# STM32F4_OSD_V12.net
KiCad netlist of a schematic drawn in Altium Designer
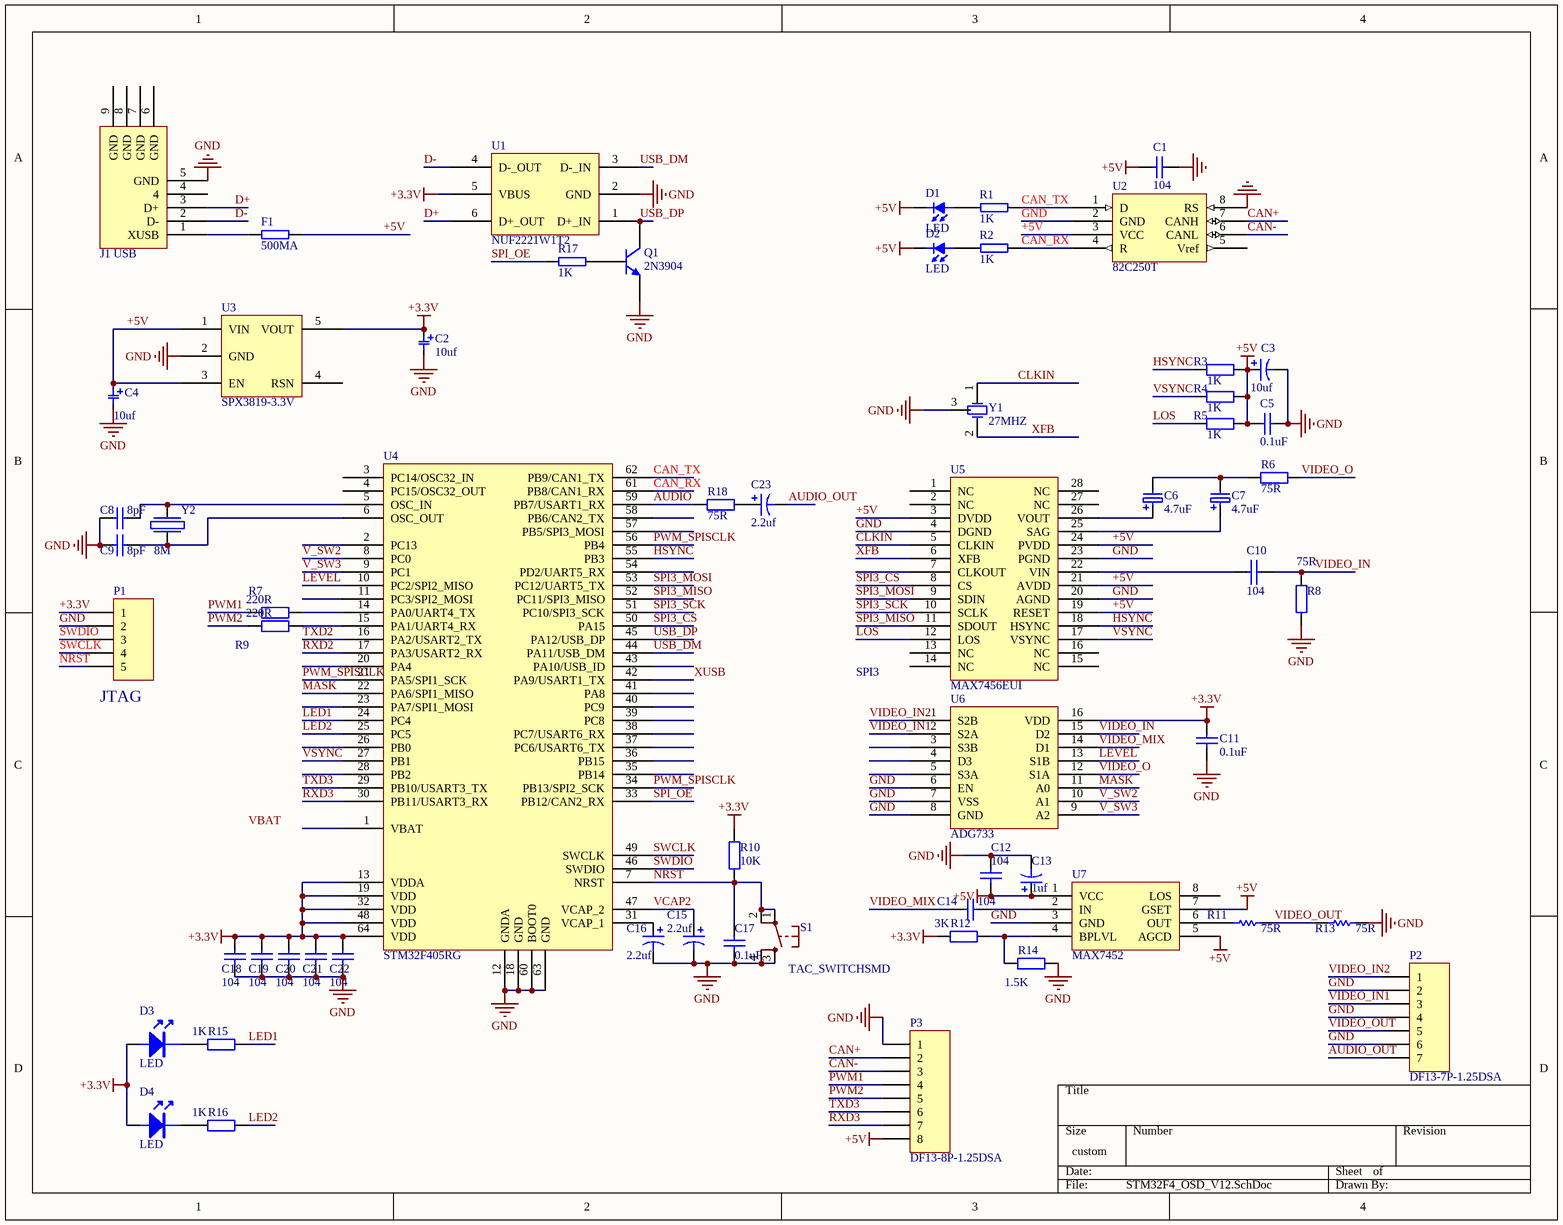
[diagram p0: STM32F4_OSD_V12.SchDoc]

(export (version "E")
  (design (tool "Eeschema 10.0.6"))
  (components
    (comp (ref "C1")
      (value "104")
      (footprint "0603C")
      (description "Capacitor")
      (fields (field (name "PUBLISHER") "Altium Limited"))
      (libsource (lib "") (part "CAP_1"))
    )
    (comp (ref "C2") (value "10uf") (footprint "0805") (libsource (lib "电阻电容") (part "ECAP")))
    (comp (ref "C3")
      (value "10uf")
      (footprint "0603C")
      (description "Polarized Capacitor (Radial)")
      (libsource (lib "Miscellaneous Devices") (part "Cap Pol1"))
    )
    (comp (ref "C4") (value "10uf") (footprint "0805") (libsource (lib "电阻电容") (part "ECAP")))
    (comp (ref "C5")
      (value "0.1uF")
      (footprint "0402-CAP")
      (description "Capacitor")
      (fields (field (name "Comment") "Cap") (field (name "PUBLISHER") "Altium Limited"))
      (libsource (lib "Miscellaneous Devices") (part "Cap"))
    )
    (comp (ref "C6")
      (value "4.7uF")
      (footprint "0603C")
      (description "Electrolytic Capacitor 1")
      (libsource (lib "QT_SCH_V2") (part "ELECTRO1"))
    )
    (comp (ref "C7")
      (value "4.7uF")
      (footprint "0603C")
      (description "Electrolytic Capacitor 1")
      (libsource (lib "QT_SCH_V2") (part "ELECTRO1"))
    )
    (comp (ref "C8")
      (value "8pF")
      (footprint "0402-CAP")
      (description "Capacitor")
      (libsource (lib "EMotus Components") (part "CAP0805"))
    )
    (comp (ref "C9")
      (value "8pF")
      (footprint "0402-CAP")
      (description "Capacitor")
      (libsource (lib "EMotus Components") (part "CAP0805"))
    )
    (comp (ref "C10")
      (value "104")
      (footprint "0402-CAP")
      (description "Capacitor")
      (libsource (lib "*") (part "CAP"))
    )
    (comp (ref "C11")
      (value "0.1uF")
      (footprint "0402-CAP")
      (description "Capacitor")
      (fields (field (name "Comment") "Cap") (field (name "PUBLISHER") "Altium Limited"))
      (libsource (lib "Miscellaneous Devices") (part "Cap"))
    )
    (comp (ref "C12")
      (value "104")
      (footprint "0402-CAP")
      (description "Capacitor")
      (libsource (lib "Miscellaneous Devices") (part "Cap"))
    )
    (comp (ref "C13")
      (value "1uf")
      (footprint "0603C")
      (description "Polarized Capacitor (Radial)")
      (libsource (lib "Miscellaneous Devices") (part "Cap Pol1"))
    )
    (comp (ref "C14")
      (value "104")
      (footprint "0402-CAP")
      (description "Capacitor")
      (libsource (lib "Miscellaneous Devices") (part "Cap"))
    )
    (comp (ref "C15")
      (value "2.2uf")
      (footprint "0603C")
      (description "Polarized Capacitor (Radial)")
      (libsource (lib "Miscellaneous Devices") (part "Cap Pol1"))
    )
    (comp (ref "C16")
      (value "2.2uf")
      (footprint "0603C")
      (description "Polarized Capacitor (Radial)")
      (libsource (lib "Miscellaneous Devices") (part "Cap Pol1"))
    )
    (comp (ref "C17")
      (value "0.1uF")
      (footprint "0402-CAP")
      (description "Capacitor")
      (fields (field (name "Comment") "Cap") (field (name "PUBLISHER") "Altium Limited"))
      (libsource (lib "Miscellaneous Devices") (part "Cap"))
    )
    (comp (ref "C18")
      (value "104")
      (footprint "0402-CAP")
      (description "Capacitor")
      (libsource (lib "Miscellaneous Devices") (part "Cap"))
    )
    (comp (ref "C19")
      (value "104")
      (footprint "0402-CAP")
      (description "Capacitor")
      (libsource (lib "Miscellaneous Devices") (part "Cap"))
    )
    (comp (ref "C20")
      (value "104")
      (footprint "0402-CAP")
      (description "Capacitor")
      (libsource (lib "Miscellaneous Devices") (part "Cap"))
    )
    (comp (ref "C21")
      (value "104")
      (footprint "0402-CAP")
      (description "Capacitor")
      (libsource (lib "Miscellaneous Devices") (part "Cap"))
    )
    (comp (ref "C22")
      (value "104")
      (footprint "0402-CAP")
      (description "Capacitor")
      (libsource (lib "Miscellaneous Devices") (part "Cap"))
    )
    (comp (ref "C23")
      (value "2.2uf")
      (footprint "0603C")
      (description "Polarized Capacitor (Radial)")
      (libsource (lib "Miscellaneous Devices") (part "Cap Pol1"))
    )
    (comp (ref "D1") (value "LED") (footprint "0603-LED") (libsource (lib "原理图库") (part "LED")))
    (comp (ref "D2") (value "LED") (footprint "0603-LED") (libsource (lib "原理图库") (part "LED")))
    (comp (ref "D3") (value "LED") (footprint "0603-LED") (libsource (lib "MySch") (part "LED")))
    (comp (ref "D4") (value "LED") (footprint "0603-LED") (libsource (lib "MySch") (part "LED")))
    (comp (ref "F1") (value "500MA") (footprint "PTC-1206") (libsource (lib "DXP常用原理图库.libsch") (part "RES")))
    (comp (ref "J1")
      (value "USB")
      (footprint "MOLEX_MICRO_USB_AB_BOTTOM_MOUNT")
      (libsource (lib "Schlib1") (part "USB"))
    )
    (comp (ref "P1")
      (value "JTAG")
      (footprint "DF13-5P-1.25DSA")
      (description "Header, 5-Pin")
      (libsource (lib "Miscellaneous Connectors") (part "Header 5"))
    )
    (comp (ref "P2")
      (value "DF13-7P-1.25DSA")
      (footprint "DF13C-7P-1.25V")
      (description "Header, 7-Pin")
      (libsource (lib "Miscellaneous Connectors") (part "Header 7"))
    )
    (comp (ref "P3")
      (value "DF13-8P-1.25DSA")
      (footprint "DF13C-8P-1.25V")
      (description "Header, 8-Pin")
      (libsource (lib "Miscellaneous Connectors") (part "Header 8"))
    )
    (comp (ref "Q1")
      (value "2N3904")
      (footprint "TO-92A")
      (description "NPN General Purpose Amplifier")
      (fields (field (name "PUBLISHER") "Altium Limited"))
      (libsource (lib "Miscellaneous Devices") (part "2N3904"))
    )
    (comp (ref "R1") (value "1K") (footprint "0402-RES") (libsource (lib "DXP常用原理图库.libsch") (part "RES")))
    (comp (ref "R2") (value "1K") (footprint "0402-RES") (libsource (lib "DXP常用原理图库.libsch") (part "RES")))
    (comp (ref "R3")
      (value "1K")
      (footprint "0402-RES")
      (description "Resistor")
      (libsource (lib "") (part "Res2_1"))
    )
    (comp (ref "R4")
      (value "1K")
      (footprint "0402-RES")
      (description "Resistor")
      (libsource (lib "") (part "Res2_1"))
    )
    (comp (ref "R5")
      (value "1K")
      (footprint "0402-RES")
      (description "Resistor")
      (libsource (lib "") (part "Res2_1"))
    )
    (comp (ref "R6")
      (value "75R")
      (footprint "0402-RES")
      (description "Resistor")
      (libsource (lib "") (part "Res2_1"))
    )
    (comp (ref "R7")
      (value "220R")
      (footprint "0402-RES")
      (description "Resistor")
      (libsource (lib "Miscellaneous Devices") (part "Res2"))
    )
    (comp (ref "R8")
      (value "75R")
      (footprint "0402-RES")
      (description "Resistor")
      (libsource (lib "") (part "Res2_2"))
    )
    (comp (ref "R9")
      (value "220R")
      (footprint "0402-RES")
      (description "Resistor")
      (libsource (lib "Miscellaneous Devices") (part "Res2"))
    )
    (comp (ref "R10")
      (value "10K")
      (footprint "0402-RES")
      (description "Resistor")
      (libsource (lib "") (part "Res2_2"))
    )
    (comp (ref "R11")
      (value "75R")
      (footprint "0402-RES")
      (description "Resistor")
      (libsource (lib "Miscellaneous Devices") (part "Res1"))
    )
    (comp (ref "R12")
      (value "3K")
      (footprint "0402-RES")
      (description "Resistor")
      (libsource (lib "Miscellaneous Devices") (part "Res2"))
    )
    (comp (ref "R13")
      (value "75R")
      (footprint "0402-RES")
      (description "Resistor")
      (libsource (lib "Miscellaneous Devices") (part "Res1"))
    )
    (comp (ref "R14")
      (value "1.5K")
      (footprint "0402-RES")
      (description "Resistor")
      (libsource (lib "Miscellaneous Devices") (part "Res2"))
    )
    (comp (ref "R15")
      (value "1K")
      (footprint "0402-RES")
      (description "Resistor")
      (libsource (lib "Miscellaneous Devices") (part "Res2"))
    )
    (comp (ref "R16")
      (value "1K")
      (footprint "0402-RES")
      (description "Resistor")
      (libsource (lib "Miscellaneous Devices") (part "Res2"))
    )
    (comp (ref "R17") (value "1K") (footprint "0402-RES") (libsource (lib "DXP常用原理图库.libsch") (part "RES")))
    (comp (ref "R18")
      (value "75R")
      (footprint "0402-RES")
      (description "Resistor")
      (libsource (lib "Miscellaneous Devices") (part "Res2"))
    )
    (comp (ref "S1")
      (value "TAC_SWITCHSMD")
      (footprint "EVQP7J01K")
      (libsource (lib "DIYdrones3") (part "TAC_SWITCHSMD"))
    )
    (comp (ref "U1")
      (value "NUF2221W1T2")
      (footprint "SOT363")
      (libsource (lib "Schlib1") (part "NUF2221W1T2"))
    )
    (comp (ref "U2") (value "82C250T") (footprint "SO-8N") (libsource (lib "*") (part "SN65HVD230D")))
    (comp (ref "U3") (value "SPX3819-3.3V") (footprint "SOT23-5") (libsource (lib "原理图库") (part "SP6201")))
    (comp (ref "U4")
      (value "STM32F405RG")
      (footprint "LQFP64")
      (libsource (lib "Schlib1") (part "STM32F405RG"))
    )
    (comp (ref "U5") (value "MAX7456EUI") (footprint "SSOP-28") (libsource (lib "Schlib1") (part "MAX7456")))
    (comp (ref "U6") (value "ADG733") (footprint "TSOP16") (libsource (lib "Schlib1") (part "ADG733")))
    (comp (ref "U7") (value "MAX7452") (footprint "SOIC-SN8_N") (libsource (lib "Schlib1") (part "MAX7452")))
    (comp (ref "Y1") (value "27MHZ") (footprint "27MHZ") (libsource (lib "晶振滤波器") (part "晶振3脚")))
    (comp (ref "Y2")
      (value "8M")
      (footprint "OSCILLATOR-3.2X2.5")
      (description "7B-8.000MAAJ-T")
      (libsource (lib "passive") (part "ZQ_KX12B"))
    )
  )
  (nets
    (net (code "1") (name "+3.3V") (class "Default")
      (node (ref "C11") (pin "2") (pinfunction "2_2") (pintype "passive"))
      (node (ref "C18") (pin "2") (pinfunction "2_2") (pintype "passive"))
      (node (ref "C19") (pin "2") (pinfunction "2_2") (pintype "passive"))
      (node (ref "C2") (pin "2") (pintype "passive"))
      (node (ref "C20") (pin "2") (pinfunction "2_2") (pintype "passive"))
      (node (ref "C21") (pin "2") (pinfunction "2_2") (pintype "passive"))
      (node (ref "C22") (pin "2") (pinfunction "2_2") (pintype "passive"))
      (node (ref "D3") (pin "1") (pinfunction "1_1") (pintype "passive"))
      (node (ref "D4") (pin "1") (pinfunction "1_1") (pintype "passive"))
      (node (ref "P1") (pin "1") (pinfunction "1_1") (pintype "passive"))
      (node (ref "R10") (pin "2") (pinfunction "2_2") (pintype "passive"))
      (node (ref "R12") (pin "2") (pinfunction "2_2") (pintype "passive"))
      (node (ref "U1") (pin "5") (pinfunction "VBUS_5") (pintype "passive"))
      (node (ref "U3") (pin "5") (pinfunction "VOUT_5") (pintype "passive"))
      (node (ref "U4") (pin "13") (pinfunction "VDDA_13") (pintype "passive"))
      (node (ref "U4") (pin "19") (pinfunction "VDD_19") (pintype "passive"))
      (node (ref "U4") (pin "32") (pinfunction "VDD_32") (pintype "passive"))
      (node (ref "U4") (pin "48") (pinfunction "VDD_48") (pintype "passive"))
      (node (ref "U4") (pin "64") (pinfunction "VDD_64") (pintype "passive"))
      (node (ref "U6") (pin "16") (pinfunction "VDD_16") (pintype "passive"))
    )
    (net (code "2") (name "+5V") (class "Default")
      (node (ref "C1") (pin "2") (pinfunction "2_2") (pintype "passive"))
      (node (ref "C12") (pin "1") (pinfunction "1_1") (pintype "passive"))
      (node (ref "C13") (pin "1") (pinfunction "1_1") (pintype "passive"))
      (node (ref "C3") (pin "1") (pinfunction "1_1") (pintype "passive"))
      (node (ref "C4") (pin "2") (pintype "passive"))
      (node (ref "C5") (pin "1") (pinfunction "1_1") (pintype "passive"))
      (node (ref "D1") (pin "2") (pinfunction "2_2") (pintype "passive"))
      (node (ref "D2") (pin "2") (pinfunction "2_2") (pintype "passive"))
      (node (ref "F1") (pin "1") (pinfunction "1_1") (pintype "passive"))
      (node (ref "P3") (pin "8") (pinfunction "8_8") (pintype "passive"))
      (node (ref "R3") (pin "2") (pinfunction "2_2") (pintype "passive"))
      (node (ref "R4") (pin "2") (pinfunction "2_2") (pintype "passive"))
      (node (ref "R5") (pin "2") (pinfunction "2_2") (pintype "passive"))
      (node (ref "U2") (pin "3") (pinfunction "VCC_3") (pintype "power_in"))
      (node (ref "U3") (pin "1") (pinfunction "VIN_1") (pintype "passive"))
      (node (ref "U3") (pin "3") (pinfunction "EN_3") (pintype "passive"))
      (node (ref "U5") (pin "19") (pinfunction "RESET_19") (pintype "passive"))
      (node (ref "U5") (pin "21") (pinfunction "AVDD_21") (pintype "passive"))
      (node (ref "U5") (pin "24") (pinfunction "PVDD_24") (pintype "passive"))
      (node (ref "U5") (pin "3") (pinfunction "DVDD_3") (pintype "passive"))
      (node (ref "U7") (pin "1") (pinfunction "VCC_1") (pintype "passive"))
      (node (ref "U7") (pin "5") (pinfunction "AGCD_5") (pintype "passive"))
      (node (ref "U7") (pin "7") (pinfunction "GSET_7") (pintype "passive"))
    )
    (net (code "3") (name "/AUDIO") (class "Default")
      (node (ref "R18") (pin "2") (pinfunction "2_2") (pintype "passive"))
      (node (ref "U4") (pin "59") (pinfunction "PB7/USART1_RX_59") (pintype "passive"))
    )
    (net (code "4") (name "/AUDIO_OUT") (class "Default")
      (node (ref "C23") (pin "2") (pinfunction "2_2") (pintype "passive"))
      (node (ref "P2") (pin "7") (pinfunction "7_7") (pintype "passive"))
    )
    (net (code "5") (name "/CAN+") (class "Default")
      (node (ref "P3") (pin "2") (pinfunction "2_2") (pintype "passive"))
      (node (ref "U2") (pin "7") (pinfunction "CANH_7") (pintype "bidirectional"))
    )
    (net (code "6") (name "/CAN-") (class "Default")
      (node (ref "P3") (pin "3") (pinfunction "3_3") (pintype "passive"))
      (node (ref "U2") (pin "6") (pinfunction "CANL_6") (pintype "bidirectional"))
    )
    (net (code "7") (name "/CAN_RX") (class "Default")
      (node (ref "R2") (pin "2") (pinfunction "2_2") (pintype "passive"))
      (node (ref "U2") (pin "4") (pinfunction "R_4") (pintype "output"))
      (node (ref "U4") (pin "61") (pinfunction "PB8/CAN1_RX_61") (pintype "passive"))
    )
    (net (code "8") (name "/CAN_TX") (class "Default")
      (node (ref "R1") (pin "2") (pinfunction "2_2") (pintype "passive"))
      (node (ref "U2") (pin "1") (pinfunction "D_1") (pintype "input"))
      (node (ref "U4") (pin "62") (pinfunction "PB9/CAN1_TX_62") (pintype "passive"))
    )
    (net (code "9") (name "/CLKIN") (class "Default")
      (node (ref "U5") (pin "5") (pinfunction "CLKIN_5") (pintype "passive"))
      (node (ref "Y1") (pin "1") (pinfunction "1_1") (pintype "passive"))
    )
    (net (code "10") (name "/D+") (class "Default")
      (node (ref "J1") (pin "3") (pinfunction "D+_3") (pintype "passive"))
      (node (ref "U1") (pin "6") (pinfunction "D+_OUT_6") (pintype "passive"))
    )
    (net (code "11") (name "/D-") (class "Default")
      (node (ref "J1") (pin "2") (pinfunction "D-_2") (pintype "passive"))
      (node (ref "U1") (pin "4") (pinfunction "D-_OUT_4") (pintype "passive"))
    )
    (net (code "12") (name "/HSYNC") (class "Default")
      (node (ref "R3") (pin "1") (pinfunction "1_1") (pintype "passive"))
      (node (ref "U4") (pin "55") (pinfunction "PB3_55") (pintype "passive"))
      (node (ref "U5") (pin "18") (pinfunction "HSYNC_18") (pintype "passive"))
    )
    (net (code "13") (name "/LED1") (class "Default")
      (node (ref "R15") (pin "1") (pinfunction "1_1") (pintype "passive"))
      (node (ref "U4") (pin "24") (pinfunction "PC4_24") (pintype "passive"))
    )
    (net (code "14") (name "/LED2") (class "Default")
      (node (ref "R16") (pin "1") (pinfunction "1_1") (pintype "passive"))
      (node (ref "U4") (pin "25") (pinfunction "PC5_25") (pintype "passive"))
    )
    (net (code "15") (name "/LEVEL") (class "Default")
      (node (ref "U4") (pin "10") (pinfunction "PC2/SPI2_MISO_10") (pintype "passive"))
      (node (ref "U6") (pin "13") (pinfunction "S1B_13") (pintype "passive"))
    )
    (net (code "16") (name "/LOS") (class "Default")
      (node (ref "R5") (pin "1") (pinfunction "1_1") (pintype "passive"))
      (node (ref "U5") (pin "12") (pinfunction "LOS_12") (pintype "passive"))
    )
    (net (code "17") (name "/MASK") (class "Default")
      (node (ref "U4") (pin "22") (pinfunction "PA6/SPI1_MISO_22") (pintype "passive"))
      (node (ref "U6") (pin "11") (pinfunction "A0_11") (pintype "passive"))
    )
    (net (code "18") (name "/NRST") (class "Default")
      (node (ref "C17") (pin "2") (pinfunction "2_2") (pintype "passive"))
      (node (ref "P1") (pin "5") (pinfunction "5_5") (pintype "passive"))
      (node (ref "R10") (pin "1") (pinfunction "1_1") (pintype "passive"))
      (node (ref "S1") (pin "1") (pinfunction "1_1") (pintype "passive"))
      (node (ref "S1") (pin "2") (pinfunction "2_2") (pintype "passive"))
      (node (ref "U4") (pin "7") (pinfunction "NRST_7") (pintype "passive"))
    )
    (net (code "19") (name "/PWM1") (class "Default")
      (node (ref "P3") (pin "4") (pinfunction "4_4") (pintype "passive"))
      (node (ref "R7") (pin "2") (pinfunction "2_2") (pintype "passive"))
    )
    (net (code "20") (name "/PWM2") (class "Default")
      (node (ref "P3") (pin "5") (pinfunction "5_5") (pintype "passive"))
      (node (ref "R9") (pin "2") (pinfunction "2_2") (pintype "passive"))
    )
    (net (code "21") (name "/PWM_SPISCLK") (class "Default")
      (node (ref "U4") (pin "21") (pinfunction "PA5/SPI1_SCK_21") (pintype "passive"))
      (node (ref "U4") (pin "34") (pinfunction "PB13/SPI2_SCK_34") (pintype "passive"))
      (node (ref "U4") (pin "56") (pinfunction "PB4_56") (pintype "passive"))
    )
    (net (code "22") (name "/RXD2") (class "Default")
      (node (ref "U4") (pin "17") (pinfunction "PA3/USART2_RX_17") (pintype "passive"))
    )
    (net (code "23") (name "/RXD3") (class "Default")
      (node (ref "P3") (pin "7") (pinfunction "7_7") (pintype "passive"))
      (node (ref "U4") (pin "30") (pinfunction "PB11/USART3_RX_30") (pintype "passive"))
    )
    (net (code "24") (name "/SPI3_CS") (class "Default")
      (node (ref "U4") (pin "50") (pinfunction "PA15_50") (pintype "passive"))
      (node (ref "U5") (pin "8") (pinfunction "CS_8") (pintype "passive"))
    )
    (net (code "25") (name "/SPI3_MISO") (class "Default")
      (node (ref "U4") (pin "52") (pinfunction "PC11/SPI3_MISO_52") (pintype "passive"))
      (node (ref "U5") (pin "11") (pinfunction "SDOUT_11") (pintype "passive"))
    )
    (net (code "26") (name "/SPI3_MOSI") (class "Default")
      (node (ref "U4") (pin "53") (pinfunction "PC12/UART5_TX_53") (pintype "passive"))
      (node (ref "U5") (pin "9") (pinfunction "SDIN_9") (pintype "passive"))
    )
    (net (code "27") (name "/SPI3_SCK") (class "Default")
      (node (ref "U4") (pin "51") (pinfunction "PC10/SPI3_SCK_51") (pintype "passive"))
      (node (ref "U5") (pin "10") (pinfunction "SCLK_10") (pintype "passive"))
    )
    (net (code "28") (name "/SPI_OE") (class "Default")
      (node (ref "R17") (pin "1") (pinfunction "1_1") (pintype "passive"))
      (node (ref "U4") (pin "33") (pinfunction "PB12/CAN2_RX_33") (pintype "passive"))
    )
    (net (code "29") (name "/SWCLK") (class "Default")
      (node (ref "P1") (pin "4") (pinfunction "4_4") (pintype "passive"))
      (node (ref "U4") (pin "49") (pinfunction "SWCLK_49") (pintype "passive"))
    )
    (net (code "30") (name "/SWDIO") (class "Default")
      (node (ref "P1") (pin "3") (pinfunction "3_3") (pintype "passive"))
      (node (ref "U4") (pin "46") (pinfunction "SWDIO_46") (pintype "passive"))
    )
    (net (code "31") (name "/TXD2") (class "Default")
      (node (ref "U4") (pin "16") (pinfunction "PA2/USART2_TX_16") (pintype "passive"))
    )
    (net (code "32") (name "/TXD3") (class "Default")
      (node (ref "P3") (pin "6") (pinfunction "6_6") (pintype "passive"))
      (node (ref "U4") (pin "29") (pinfunction "PB10/USART3_TX_29") (pintype "passive"))
    )
    (net (code "33") (name "/USB_DM") (class "Default")
      (node (ref "U1") (pin "3") (pinfunction "D-_IN_3") (pintype "passive"))
      (node (ref "U4") (pin "44") (pinfunction "PA11/USB_DM_44") (pintype "passive"))
    )
    (net (code "34") (name "/USB_DP") (class "Default")
      (node (ref "Q1") (pin "3") (pinfunction "C_3") (pintype "passive"))
      (node (ref "U1") (pin "1") (pinfunction "D+_IN_1") (pintype "passive"))
      (node (ref "U4") (pin "45") (pinfunction "PA12/USB_DP_45") (pintype "passive"))
    )
    (net (code "36") (name "/VCAP2") (class "Default")
      (node (ref "C15") (pin "1") (pinfunction "1_1") (pintype "passive"))
      (node (ref "U4") (pin "47") (pinfunction "VCAP_2_47") (pintype "passive"))
    )
    (net (code "37") (name "/VIDEO_IN") (class "Default")
      (node (ref "C10") (pin "2") (pinfunction "2_2") (pintype "passive"))
      (node (ref "R8") (pin "2") (pinfunction "2_2") (pintype "passive"))
      (node (ref "U6") (pin "15") (pinfunction "D2_15") (pintype "passive"))
    )
    (net (code "38") (name "/VIDEO_IN1") (class "Default")
      (node (ref "P2") (pin "3") (pinfunction "3_3") (pintype "passive"))
      (node (ref "U6") (pin "2") (pinfunction "S2A_2") (pintype "passive"))
    )
    (net (code "39") (name "/VIDEO_IN2") (class "Default")
      (node (ref "P2") (pin "1") (pinfunction "1_1") (pintype "passive"))
      (node (ref "U6") (pin "1") (pinfunction "S2B_1") (pintype "passive"))
    )
    (net (code "40") (name "/VIDEO_MIX") (class "Default")
      (node (ref "C14") (pin "1") (pinfunction "1_1") (pintype "passive"))
      (node (ref "U6") (pin "14") (pinfunction "D1_14") (pintype "passive"))
    )
    (net (code "41") (name "/VIDEO_O") (class "Default")
      (node (ref "R6") (pin "2") (pinfunction "2_2") (pintype "passive"))
      (node (ref "U6") (pin "12") (pinfunction "S1A_12") (pintype "passive"))
    )
    (net (code "42") (name "/VIDEO_OUT") (class "Default")
      (node (ref "P2") (pin "5") (pinfunction "5_5") (pintype "passive"))
      (node (ref "R11") (pin "1") (pinfunction "1_1") (pintype "passive"))
      (node (ref "R13") (pin "2") (pinfunction "2_2") (pintype "passive"))
    )
    (net (code "43") (name "/VSYNC") (class "Default")
      (node (ref "R4") (pin "1") (pinfunction "1_1") (pintype "passive"))
      (node (ref "U4") (pin "27") (pinfunction "PB1_27") (pintype "passive"))
      (node (ref "U5") (pin "17") (pinfunction "VSYNC_17") (pintype "passive"))
    )
    (net (code "44") (name "/V_SW2") (class "Default")
      (node (ref "U4") (pin "8") (pinfunction "PC0_8") (pintype "passive"))
      (node (ref "U6") (pin "10") (pinfunction "A1_10") (pintype "passive"))
    )
    (net (code "45") (name "/V_SW3") (class "Default")
      (node (ref "U4") (pin "9") (pinfunction "PC1_9") (pintype "passive"))
      (node (ref "U6") (pin "9") (pinfunction "A2_9") (pintype "passive"))
    )
    (net (code "46") (name "/XFB") (class "Default")
      (node (ref "U5") (pin "6") (pinfunction "XFB_6") (pintype "passive"))
      (node (ref "Y1") (pin "2") (pinfunction "2_2") (pintype "passive"))
    )
    (net (code "47") (name "/XUSB") (class "Default")
      (node (ref "U4") (pin "42") (pinfunction "PA9/USART1_TX_42") (pintype "passive"))
    )
    (net (code "48") (name "GND") (class "Default")
      (node (ref "C1") (pin "1") (pinfunction "1_1") (pintype "passive"))
      (node (ref "C11") (pin "1") (pinfunction "1_1") (pintype "passive"))
      (node (ref "C12") (pin "2") (pinfunction "2_2") (pintype "passive"))
      (node (ref "C13") (pin "2") (pinfunction "2_2") (pintype "passive"))
      (node (ref "C15") (pin "2") (pinfunction "2_2") (pintype "passive"))
      (node (ref "C16") (pin "2") (pinfunction "2_2") (pintype "passive"))
      (node (ref "C17") (pin "1") (pinfunction "1_1") (pintype "passive"))
      (node (ref "C18") (pin "1") (pinfunction "1_1") (pintype "passive"))
      (node (ref "C19") (pin "1") (pinfunction "1_1") (pintype "passive"))
      (node (ref "C2") (pin "1") (pintype "passive"))
      (node (ref "C20") (pin "1") (pinfunction "1_1") (pintype "passive"))
      (node (ref "C21") (pin "1") (pinfunction "1_1") (pintype "passive"))
      (node (ref "C22") (pin "1") (pinfunction "1_1") (pintype "passive"))
      (node (ref "C3") (pin "2") (pinfunction "2_2") (pintype "passive"))
      (node (ref "C4") (pin "1") (pintype "passive"))
      (node (ref "C5") (pin "2") (pinfunction "2_2") (pintype "passive"))
      (node (ref "C8") (pin "2") (pinfunction "2_2") (pintype "passive"))
      (node (ref "C9") (pin "2") (pinfunction "2_2") (pintype "passive"))
      (node (ref "J1") (pin "5") (pinfunction "GND_5") (pintype "passive"))
      (node (ref "P1") (pin "2") (pinfunction "2_2") (pintype "passive"))
      (node (ref "P2") (pin "2") (pinfunction "2_2") (pintype "passive"))
      (node (ref "P2") (pin "4") (pinfunction "4_4") (pintype "passive"))
      (node (ref "P2") (pin "6") (pinfunction "6_6") (pintype "passive"))
      (node (ref "P3") (pin "1") (pinfunction "1_1") (pintype "passive"))
      (node (ref "Q1") (pin "1") (pinfunction "E_1") (pintype "passive"))
      (node (ref "R13") (pin "1") (pinfunction "1_1") (pintype "passive"))
      (node (ref "R14") (pin "1") (pinfunction "1_1") (pintype "passive"))
      (node (ref "R8") (pin "1") (pinfunction "1_1") (pintype "passive"))
      (node (ref "S1") (pin "3") (pinfunction "3_3") (pintype "passive"))
      (node (ref "S1") (pin "4") (pinfunction "4_4") (pintype "passive"))
      (node (ref "U1") (pin "2") (pinfunction "GND_2") (pintype "passive"))
      (node (ref "U2") (pin "2") (pinfunction "GND_2") (pintype "power_in"))
      (node (ref "U2") (pin "8") (pinfunction "RS_8") (pintype "input"))
      (node (ref "U3") (pin "2") (pinfunction "GND_2") (pintype "passive"))
      (node (ref "U4") (pin "12") (pinfunction "GNDA_12") (pintype "passive"))
      (node (ref "U4") (pin "18") (pinfunction "GND_18") (pintype "passive"))
      (node (ref "U4") (pin "60") (pinfunction "BOOT0_60") (pintype "passive"))
      (node (ref "U4") (pin "63") (pinfunction "GND_63") (pintype "passive"))
      (node (ref "U5") (pin "20") (pinfunction "AGND_20") (pintype "passive"))
      (node (ref "U5") (pin "23") (pinfunction "PGND_23") (pintype "passive"))
      (node (ref "U5") (pin "4") (pinfunction "DGND_4") (pintype "passive"))
      (node (ref "U6") (pin "6") (pinfunction "EN_6") (pintype "passive"))
      (node (ref "U6") (pin "7") (pinfunction "VSS_7") (pintype "passive"))
      (node (ref "U6") (pin "8") (pinfunction "GND_8") (pintype "passive"))
      (node (ref "U7") (pin "3") (pinfunction "GND_3") (pintype "passive"))
      (node (ref "Y1") (pin "3") (pinfunction "3_3") (pintype "passive"))
    )
    (net (code "49") (name "Net-(C6-Pad2)") (class "Default")
      (node (ref "C6") (pin "2") (pinfunction "2_2") (pintype "passive"))
      (node (ref "C7") (pin "2") (pinfunction "2_2") (pintype "passive"))
      (node (ref "R6") (pin "1") (pinfunction "1_1") (pintype "passive"))
    )
    (net (code "50") (name "Net-(C23-Pad1)") (class "Default")
      (node (ref "C23") (pin "1") (pinfunction "1_1") (pintype "passive"))
      (node (ref "R18") (pin "1") (pinfunction "1_1") (pintype "passive"))
    )
    (net (code "51") (name "Net-(D1-Pad1)") (class "Default")
      (node (ref "D1") (pin "1") (pinfunction "1_1") (pintype "passive"))
      (node (ref "R1") (pin "1") (pinfunction "1_1") (pintype "passive"))
    )
    (net (code "52") (name "Net-(D2-Pad1)") (class "Default")
      (node (ref "D2") (pin "1") (pinfunction "1_1") (pintype "passive"))
      (node (ref "R2") (pin "1") (pinfunction "1_1") (pintype "passive"))
    )
    (net (code "53") (name "Net-(D3-Pad2)") (class "Default")
      (node (ref "D3") (pin "2") (pinfunction "2_2") (pintype "passive"))
      (node (ref "R15") (pin "2") (pinfunction "2_2") (pintype "passive"))
    )
    (net (code "54") (name "Net-(D4-Pad2)") (class "Default")
      (node (ref "D4") (pin "2") (pinfunction "2_2") (pintype "passive"))
      (node (ref "R16") (pin "2") (pinfunction "2_2") (pintype "passive"))
    )
    (net (code "55") (name "Net-(J1-XUSB)") (class "Default")
      (node (ref "F1") (pin "2") (pinfunction "2_2") (pintype "passive"))
      (node (ref "J1") (pin "1") (pinfunction "XUSB_1") (pintype "passive"))
    )
    (net (code "56") (name "Net-(Q1-B)") (class "Default")
      (node (ref "Q1") (pin "2") (pinfunction "B_2") (pintype "passive"))
      (node (ref "R17") (pin "2") (pinfunction "2_2") (pintype "passive"))
    )
    (net (code "57") (name "Net-(U4-OSC_IN)") (class "Default")
      (node (ref "C8") (pin "1") (pinfunction "1_1") (pintype "passive"))
      (node (ref "U4") (pin "5") (pinfunction "OSC_IN_5") (pintype "passive"))
      (node (ref "Y2") (pin "1") (pinfunction "1_1") (pintype "passive"))
    )
    (net (code "58") (name "Net-(U4-OSC_OUT)") (class "Default")
      (node (ref "C9") (pin "1") (pinfunction "1_1") (pintype "passive"))
      (node (ref "U4") (pin "6") (pinfunction "OSC_OUT_6") (pintype "passive"))
      (node (ref "Y2") (pin "2") (pinfunction "2_2") (pintype "passive"))
    )
    (net (code "59") (name "Net-(U4-PA0{slash}UART4_TX)") (class "Default")
      (node (ref "R7") (pin "1") (pinfunction "1_1") (pintype "passive"))
      (node (ref "U4") (pin "14") (pinfunction "PA0/UART4_TX_14") (pintype "passive"))
    )
    (net (code "60") (name "Net-(U4-PA1{slash}UART4_RX)") (class "Default")
      (node (ref "R9") (pin "1") (pinfunction "1_1") (pintype "passive"))
      (node (ref "U4") (pin "15") (pinfunction "PA1/UART4_RX_15") (pintype "passive"))
    )
    (net (code "61") (name "Net-(U4-VCAP_1)") (class "Default")
      (node (ref "C16") (pin "1") (pinfunction "1_1") (pintype "passive"))
      (node (ref "U4") (pin "31") (pinfunction "VCAP_1_31") (pintype "passive"))
    )
    (net (code "62") (name "Net-(U5-SAG)") (class "Default")
      (node (ref "C7") (pin "1") (pinfunction "1_1") (pintype "passive"))
      (node (ref "U5") (pin "25") (pinfunction "SAG_25") (pintype "passive"))
    )
    (net (code "63") (name "Net-(U5-VIN)") (class "Default")
      (node (ref "C10") (pin "1") (pinfunction "1_1") (pintype "passive"))
      (node (ref "U5") (pin "22") (pinfunction "VIN_22") (pintype "passive"))
    )
    (net (code "64") (name "Net-(U5-VOUT)") (class "Default")
      (node (ref "C6") (pin "1") (pinfunction "1_1") (pintype "passive"))
      (node (ref "U5") (pin "26") (pinfunction "VOUT_26") (pintype "passive"))
    )
    (net (code "65") (name "Net-(U7-BPLVL)") (class "Default")
      (node (ref "R12") (pin "1") (pinfunction "1_1") (pintype "passive"))
      (node (ref "R14") (pin "2") (pinfunction "2_2") (pintype "passive"))
      (node (ref "U7") (pin "4") (pinfunction "BPLVL_4") (pintype "passive"))
    )
    (net (code "66") (name "Net-(U7-IN)") (class "Default")
      (node (ref "C14") (pin "2") (pinfunction "2_2") (pintype "passive"))
      (node (ref "U7") (pin "2") (pinfunction "IN_2") (pintype "passive"))
    )
    (net (code "67") (name "Net-(U7-OUT)") (class "Default")
      (node (ref "R11") (pin "2") (pinfunction "2_2") (pintype "passive"))
      (node (ref "U7") (pin "6") (pinfunction "OUT_6") (pintype "passive"))
    )
    (net (code "68") (name "unconnected-(J1-GND-Pad6)") (class "Default")
      (node (ref "J1") (pin "6") (pinfunction "GND_6") (pintype "passive"))
    )
    (net (code "69") (name "unconnected-(J1-GND-Pad7)") (class "Default")
      (node (ref "J1") (pin "7") (pinfunction "GND_7") (pintype "passive"))
    )
    (net (code "70") (name "unconnected-(J1-GND-Pad8)") (class "Default")
      (node (ref "J1") (pin "8") (pinfunction "GND_8") (pintype "passive"))
    )
    (net (code "71") (name "unconnected-(J1-GND-Pad9)") (class "Default")
      (node (ref "J1") (pin "9") (pinfunction "GND_9") (pintype "passive"))
    )
    (net (code "72") (name "unconnected-(J1-Pad4)") (class "Default")
      (node (ref "J1") (pin "4") (pinfunction "4_4") (pintype "passive"))
    )
    (net (code "73") (name "unconnected-(U2-Vref-Pad5)") (class "Default")
      (node (ref "U2") (pin "5") (pinfunction "Vref_5") (pintype "output"))
    )
    (net (code "74") (name "unconnected-(U3-RSN-Pad4)") (class "Default")
      (node (ref "U3") (pin "4") (pinfunction "RSN_4") (pintype "passive"))
    )
    (net (code "75") (name "unconnected-(U4-PA4-Pad20)") (class "Default")
      (node (ref "U4") (pin "20") (pinfunction "PA4_20") (pintype "passive"))
    )
    (net (code "76") (name "unconnected-(U4-PA7{slash}SPI1_MOSI-Pad23)") (class "Default")
      (node (ref "U4") (pin "23") (pinfunction "PA7/SPI1_MOSI_23") (pintype "passive"))
    )
    (net (code "77") (name "unconnected-(U4-PA8-Pad41)") (class "Default")
      (node (ref "U4") (pin "41") (pinfunction "PA8_41") (pintype "passive"))
    )
    (net (code "78") (name "unconnected-(U4-PA10{slash}USB_ID-Pad43)") (class "Default")
      (node (ref "U4") (pin "43") (pinfunction "PA10/USB_ID_43") (pintype "passive"))
    )
    (net (code "79") (name "unconnected-(U4-PB0-Pad26)") (class "Default")
      (node (ref "U4") (pin "26") (pinfunction "PB0_26") (pintype "passive"))
    )
    (net (code "80") (name "unconnected-(U4-PB2-Pad28)") (class "Default")
      (node (ref "U4") (pin "28") (pinfunction "PB2_28") (pintype "passive"))
    )
    (net (code "81") (name "unconnected-(U4-PB5{slash}SPI3_MOSI-Pad57)") (class "Default")
      (node (ref "U4") (pin "57") (pinfunction "PB5/SPI3_MOSI_57") (pintype "passive"))
    )
    (net (code "82") (name "unconnected-(U4-PB6{slash}CAN2_TX-Pad58)") (class "Default")
      (node (ref "U4") (pin "58") (pinfunction "PB6/CAN2_TX_58") (pintype "passive"))
    )
    (net (code "83") (name "unconnected-(U4-PB14-Pad35)") (class "Default")
      (node (ref "U4") (pin "35") (pinfunction "PB14_35") (pintype "passive"))
    )
    (net (code "84") (name "unconnected-(U4-PB15-Pad36)") (class "Default")
      (node (ref "U4") (pin "36") (pinfunction "PB15_36") (pintype "passive"))
    )
    (net (code "85") (name "unconnected-(U4-PC3{slash}SPI2_MOSI-Pad11)") (class "Default")
      (node (ref "U4") (pin "11") (pinfunction "PC3/SPI2_MOSI_11") (pintype "passive"))
    )
    (net (code "86") (name "unconnected-(U4-PC6{slash}USART6_TX-Pad37)") (class "Default")
      (node (ref "U4") (pin "37") (pinfunction "PC6/USART6_TX_37") (pintype "passive"))
    )
    (net (code "87") (name "unconnected-(U4-PC7{slash}USART6_RX-Pad38)") (class "Default")
      (node (ref "U4") (pin "38") (pinfunction "PC7/USART6_RX_38") (pintype "passive"))
    )
    (net (code "88") (name "unconnected-(U4-PC8-Pad39)") (class "Default")
      (node (ref "U4") (pin "39") (pinfunction "PC8_39") (pintype "passive"))
    )
    (net (code "89") (name "unconnected-(U4-PC9-Pad40)") (class "Default")
      (node (ref "U4") (pin "40") (pinfunction "PC9_40") (pintype "passive"))
    )
    (net (code "90") (name "unconnected-(U4-PC13-Pad2)") (class "Default")
      (node (ref "U4") (pin "2") (pinfunction "PC13_2") (pintype "passive"))
    )
    (net (code "91") (name "unconnected-(U4-PC14{slash}OSC32_IN-Pad3)") (class "Default")
      (node (ref "U4") (pin "3") (pinfunction "PC14/OSC32_IN_3") (pintype "passive"))
    )
    (net (code "92") (name "unconnected-(U4-PC15{slash}OSC32_OUT-Pad4)") (class "Default")
      (node (ref "U4") (pin "4") (pinfunction "PC15/OSC32_OUT_4") (pintype "passive"))
    )
    (net (code "93") (name "unconnected-(U4-PD2{slash}UART5_RX-Pad54)") (class "Default")
      (node (ref "U4") (pin "54") (pinfunction "PD2/UART5_RX_54") (pintype "passive"))
    )
    (net (code "94") (name "unconnected-(U4-VBAT-Pad1)") (class "Default")
      (node (ref "U4") (pin "1") (pinfunction "VBAT_1") (pintype "passive"))
    )
    (net (code "95") (name "unconnected-(U5-CLKOUT-Pad7)") (class "Default")
      (node (ref "U5") (pin "7") (pinfunction "CLKOUT_7") (pintype "passive"))
    )
    (net (code "96") (name "unconnected-(U5-NC-Pad1)") (class "Default")
      (node (ref "U5") (pin "1") (pinfunction "NC_1") (pintype "passive"))
    )
    (net (code "97") (name "unconnected-(U5-NC-Pad2)") (class "Default")
      (node (ref "U5") (pin "2") (pinfunction "NC_2") (pintype "passive"))
    )
    (net (code "98") (name "unconnected-(U5-NC-Pad13)") (class "Default")
      (node (ref "U5") (pin "13") (pinfunction "NC_13") (pintype "passive"))
    )
    (net (code "99") (name "unconnected-(U5-NC-Pad14)") (class "Default")
      (node (ref "U5") (pin "14") (pinfunction "NC_14") (pintype "passive"))
    )
    (net (code "100") (name "unconnected-(U5-NC-Pad15)") (class "Default")
      (node (ref "U5") (pin "15") (pinfunction "NC_15") (pintype "passive"))
    )
    (net (code "101") (name "unconnected-(U5-NC-Pad16)") (class "Default")
      (node (ref "U5") (pin "16") (pinfunction "NC_16") (pintype "passive"))
    )
    (net (code "102") (name "unconnected-(U5-NC-Pad27)") (class "Default")
      (node (ref "U5") (pin "27") (pinfunction "NC_27") (pintype "passive"))
    )
    (net (code "103") (name "unconnected-(U5-NC-Pad28)") (class "Default")
      (node (ref "U5") (pin "28") (pinfunction "NC_28") (pintype "passive"))
    )
    (net (code "104") (name "unconnected-(U6-D3-Pad4)") (class "Default")
      (node (ref "U6") (pin "4") (pinfunction "D3_4") (pintype "passive"))
    )
    (net (code "105") (name "unconnected-(U6-S3A-Pad5)") (class "Default")
      (node (ref "U6") (pin "5") (pinfunction "S3A_5") (pintype "passive"))
    )
    (net (code "106") (name "unconnected-(U6-S3B-Pad3)") (class "Default")
      (node (ref "U6") (pin "3") (pinfunction "S3B_3") (pintype "passive"))
    )
    (net (code "107") (name "unconnected-(U7-LOS-Pad8)") (class "Default")
      (node (ref "U7") (pin "8") (pinfunction "LOS_8") (pintype "passive"))
    )
  )
)
